# AquaSchematic.net
KiCad netlist of a schematic drawn in EAGLE
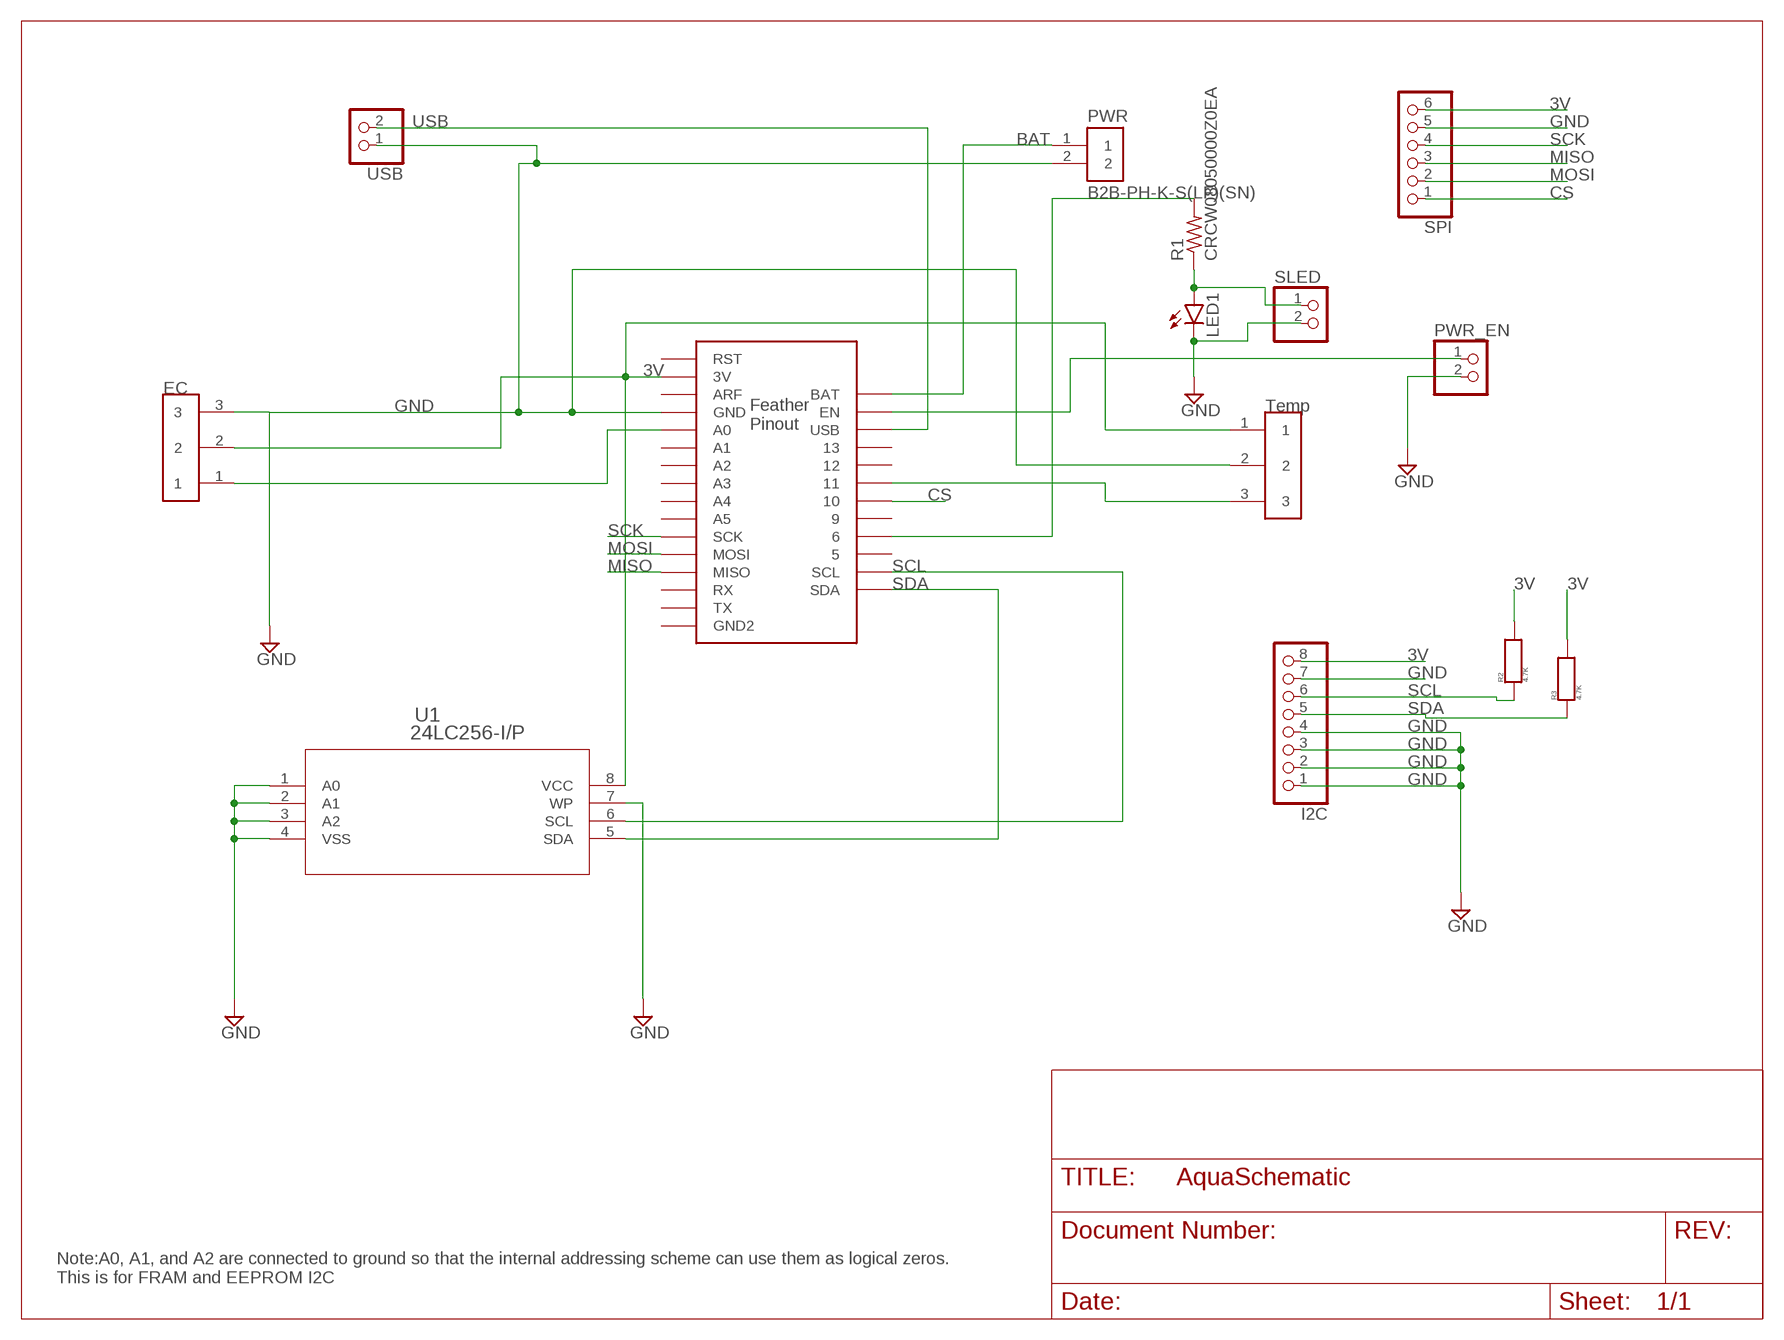
[diagram p0: schematic, sheet 1]

(export (version "E")
  (design (tool "Eeschema 10.0.6"))
  (components
    (comp (ref "EC")
      (value "39773-0003")
      (footprint "eagle-import:39773-0003")
      (libsource (lib "eagle-import") (part "39773-0003"))
    )
    (comp (ref "I2C")
      (value "PINHD-1X8")
      (footprint "eagle-import:1X08")
      (libsource (lib "eagle-import") (part "PINHD-1X8"))
    )
    (comp (ref "LED1")
      (value "LEDCHIP-LED0805")
      (footprint "eagle-import:CHIP-LED0805")
      (libsource (lib "eagle-import") (part "LEDCHIP-LED0805"))
    )
    (comp (ref "PWR")
      (value "B2B-PH-K-S(LF)(SN)")
      (footprint "eagle-import:JST_B2B-PH-K-S(LF)(SN)")
      (fields
        (field (name "DIGI-KEY_PART_NUMBER") "455-1704-ND")
        (field (name "MF") "JST Sales")
        (field (name "MP") "B2B-PH-K-S_LF__SN_")
      )
      (libsource (lib "eagle-import") (part "B2B-PH-K-S(LF)(SN)"))
    )
    (comp (ref "PWR_EN")
      (value "PINHD-1X2")
      (footprint "eagle-import:1X02")
      (libsource (lib "eagle-import") (part "PINHD-1X2"))
    )
    (comp (ref "R1")
      (value "CRCW08050000Z0EA")
      (footprint "eagle-import:RES_0805")
      (fields
        (field (name "DIGIKEY_PART_NUMBER") "541-0.0ATR-ND")
        (field (name "MANUFACTURER") "Vishay Dale")
        (field (name "CREATED_BY") "PCBLayout.com")
      )
      (libsource (lib "eagle-import") (part "CRCW08050000Z0EA"))
    )
    (comp (ref "R2")
      (value "4.7K")
      (footprint "eagle-import:MFR3-4K7FC")
      (libsource (lib "eagle-import") (part "MFR3-4K7FC"))
    )
    (comp (ref "R3")
      (value "4.7K")
      (footprint "eagle-import:MFR3-4K7FC")
      (libsource (lib "eagle-import") (part "MFR3-4K7FC"))
    )
    (comp (ref "SLED")
      (value "PINHD-1X2")
      (footprint "eagle-import:1X02")
      (libsource (lib "eagle-import") (part "PINHD-1X2"))
    )
    (comp (ref "SPI")
      (value "PINHD-1X6")
      (footprint "eagle-import:1X06")
      (libsource (lib "eagle-import") (part "PINHD-1X6"))
    )
    (comp (ref "TEMP")
      (value "39773-0003")
      (footprint "eagle-import:39773-0003")
      (libsource (lib "eagle-import") (part "39773-0003"))
    )
    (comp (ref "U$1")
      (value "FEATHER_M0_PROTO")
      (footprint "eagle-import:FEATHER_MO_PROTO")
      (libsource (lib "eagle-import") (part "FEATHER_M0_PROTO"))
    )
    (comp (ref "U1")
      (value "24LC256-I/P")
      (footprint "eagle-import:PDIP8_300MC")
      (fields (field (name "MANUFACTURER_PART_NUMBER") "24LC256IP"))
      (libsource (lib "eagle-import") (part "24LC256-I/P"))
    )
    (comp (ref "USB")
      (value "PINHD-1X2")
      (footprint "eagle-import:1X02")
      (libsource (lib "eagle-import") (part "PINHD-1X2"))
    )
  )
  (nets
    (net (code "1") (name "/3V") (class "Default")
      (node (ref "EC") (pin "2") (pinfunction "2_2") (pintype "bidirectional"))
      (node (ref "I2C") (pin "8") (pinfunction "8_8") (pintype "passive"))
      (node (ref "R2") (pin "PIN1") (pinfunction "P$1_PIN1") (pintype "bidirectional"))
      (node (ref "R3") (pin "PIN1") (pinfunction "P$1_PIN1") (pintype "bidirectional"))
      (node (ref "SPI") (pin "6") (pinfunction "6_6") (pintype "passive"))
      (node (ref "TEMP") (pin "1") (pinfunction "1_1") (pintype "bidirectional"))
      (node (ref "U$1") (pin "3V") (pinfunction "3V_3V") (pintype "bidirectional"))
      (node (ref "U1") (pin "8") (pinfunction "VCC_8") (pintype "passive"))
    )
    (net (code "2") (name "/BAT") (class "Default")
      (node (ref "PWR") (pin "1") (pinfunction "1_1") (pintype "passive"))
      (node (ref "U$1") (pin "BAT") (pinfunction "BAT_BAT") (pintype "bidirectional"))
    )
    (net (code "3") (name "/CS") (class "Default")
      (node (ref "SPI") (pin "1") (pinfunction "1_1") (pintype "passive"))
      (node (ref "U$1") (pin "10") (pinfunction "10_10") (pintype "bidirectional"))
    )
    (net (code "4") (name "/MISO") (class "Default")
      (node (ref "SPI") (pin "3") (pinfunction "3_3") (pintype "passive"))
      (node (ref "U$1") (pin "MISO") (pinfunction "MISO_MISO") (pintype "bidirectional"))
    )
    (net (code "5") (name "/MOSI") (class "Default")
      (node (ref "SPI") (pin "2") (pinfunction "2_2") (pintype "passive"))
      (node (ref "U$1") (pin "MOSI") (pinfunction "MOSI_MOSI") (pintype "bidirectional"))
    )
    (net (code "6") (name "/SCK") (class "Default")
      (node (ref "SPI") (pin "4") (pinfunction "4_4") (pintype "passive"))
      (node (ref "U$1") (pin "SCK") (pinfunction "SCK_SCK") (pintype "bidirectional"))
    )
    (net (code "7") (name "/SCL") (class "Default")
      (node (ref "I2C") (pin "6") (pinfunction "6_6") (pintype "passive"))
      (node (ref "R2") (pin "PIN2") (pinfunction "P$2_PIN2") (pintype "bidirectional"))
      (node (ref "U$1") (pin "SCL") (pinfunction "SCL_SCL") (pintype "bidirectional"))
      (node (ref "U1") (pin "6") (pinfunction "SCL_6") (pintype "passive"))
    )
    (net (code "8") (name "/SDA") (class "Default")
      (node (ref "I2C") (pin "5") (pinfunction "5_5") (pintype "passive"))
      (node (ref "R3") (pin "PIN2") (pinfunction "P$2_PIN2") (pintype "bidirectional"))
      (node (ref "U$1") (pin "SDA") (pinfunction "SDA_SDA") (pintype "bidirectional"))
      (node (ref "U1") (pin "5") (pinfunction "SDA_5") (pintype "passive"))
    )
    (net (code "9") (name "/USB") (class "Default")
      (node (ref "U$1") (pin "USB") (pinfunction "USB_USB") (pintype "bidirectional"))
      (node (ref "USB") (pin "2") (pinfunction "2_2") (pintype "passive"))
    )
    (net (code "10") (name "GND") (class "Default")
      (node (ref "EC") (pin "3") (pinfunction "3_3") (pintype "bidirectional"))
      (node (ref "I2C") (pin "1") (pinfunction "1_1") (pintype "passive"))
      (node (ref "I2C") (pin "2") (pinfunction "2_2") (pintype "passive"))
      (node (ref "I2C") (pin "3") (pinfunction "3_3") (pintype "passive"))
      (node (ref "I2C") (pin "4") (pinfunction "4_4") (pintype "passive"))
      (node (ref "I2C") (pin "7") (pinfunction "7_7") (pintype "passive"))
      (node (ref "LED1") (pin "C") (pinfunction "C_C") (pintype "passive"))
      (node (ref "PWR") (pin "2") (pinfunction "2_2") (pintype "passive"))
      (node (ref "PWR_EN") (pin "2") (pinfunction "2_2") (pintype "passive"))
      (node (ref "SLED") (pin "2") (pinfunction "2_2") (pintype "passive"))
      (node (ref "SPI") (pin "5") (pinfunction "5_5") (pintype "passive"))
      (node (ref "TEMP") (pin "2") (pinfunction "2_2") (pintype "bidirectional"))
      (node (ref "U$1") (pin "GND") (pinfunction "GND_GND") (pintype "bidirectional"))
      (node (ref "U1") (pin "1") (pinfunction "A0_1") (pintype "passive"))
      (node (ref "U1") (pin "2") (pinfunction "A1_2") (pintype "passive"))
      (node (ref "U1") (pin "3") (pinfunction "A2_3") (pintype "passive"))
      (node (ref "U1") (pin "4") (pinfunction "VSS_4") (pintype "passive"))
      (node (ref "U1") (pin "7") (pinfunction "WP_7") (pintype "passive"))
      (node (ref "USB") (pin "1") (pinfunction "1_1") (pintype "passive"))
    )
    (net (code "11") (name "Net-(EC-Pad1)") (class "Default")
      (node (ref "EC") (pin "1") (pinfunction "1_1") (pintype "bidirectional"))
      (node (ref "U$1") (pin "A0") (pinfunction "A0_A0") (pintype "bidirectional"))
    )
    (net (code "12") (name "Net-(LED1-PadA)") (class "Default")
      (node (ref "LED1") (pin "A") (pinfunction "A_A") (pintype "passive"))
      (node (ref "R1") (pin "1") (pinfunction "1_1") (pintype "passive"))
      (node (ref "SLED") (pin "1") (pinfunction "1_1") (pintype "passive"))
    )
    (net (code "13") (name "Net-(PWR_EN-Pad1)") (class "Default")
      (node (ref "PWR_EN") (pin "1") (pinfunction "1_1") (pintype "passive"))
      (node (ref "U$1") (pin "EN") (pinfunction "EN_EN") (pintype "bidirectional"))
    )
    (net (code "14") (name "Net-(R1-Pad2)") (class "Default")
      (node (ref "R1") (pin "2") (pinfunction "2_2") (pintype "passive"))
      (node (ref "U$1") (pin "6") (pinfunction "6_6") (pintype "bidirectional"))
    )
    (net (code "15") (name "Net-(TEMP-Pad3)") (class "Default")
      (node (ref "TEMP") (pin "3") (pinfunction "3_3") (pintype "bidirectional"))
      (node (ref "U$1") (pin "11") (pinfunction "11_11") (pintype "bidirectional"))
    )
    (net (code "16") (name "unconnected-(U$1-Pad5)") (class "Default")
      (node (ref "U$1") (pin "5") (pinfunction "5_5") (pintype "bidirectional"))
    )
    (net (code "17") (name "unconnected-(U$1-Pad9)") (class "Default")
      (node (ref "U$1") (pin "9") (pinfunction "9_9") (pintype "bidirectional"))
    )
    (net (code "18") (name "unconnected-(U$1-Pad12)") (class "Default")
      (node (ref "U$1") (pin "12") (pinfunction "12_12") (pintype "bidirectional"))
    )
    (net (code "19") (name "unconnected-(U$1-Pad13)") (class "Default")
      (node (ref "U$1") (pin "13") (pinfunction "13_13") (pintype "bidirectional"))
    )
    (net (code "20") (name "unconnected-(U$1-PadA1)") (class "Default")
      (node (ref "U$1") (pin "A1") (pinfunction "A1_A1") (pintype "bidirectional"))
    )
    (net (code "21") (name "unconnected-(U$1-PadA2)") (class "Default")
      (node (ref "U$1") (pin "A2") (pinfunction "A2_A2") (pintype "bidirectional"))
    )
    (net (code "22") (name "unconnected-(U$1-PadA3)") (class "Default")
      (node (ref "U$1") (pin "A3") (pinfunction "A3_A3") (pintype "bidirectional"))
    )
    (net (code "23") (name "unconnected-(U$1-PadA4)") (class "Default")
      (node (ref "U$1") (pin "A4") (pinfunction "A4_A4") (pintype "bidirectional"))
    )
    (net (code "24") (name "unconnected-(U$1-PadA5)") (class "Default")
      (node (ref "U$1") (pin "A5") (pinfunction "A5_A5") (pintype "bidirectional"))
    )
    (net (code "25") (name "unconnected-(U$1-PadARF)") (class "Default")
      (node (ref "U$1") (pin "ARF") (pinfunction "ARF_ARF") (pintype "bidirectional"))
    )
    (net (code "26") (name "unconnected-(U$1-PadGND2)") (class "Default")
      (node (ref "U$1") (pin "GND2") (pinfunction "GND2_GND2") (pintype "bidirectional"))
    )
    (net (code "27") (name "unconnected-(U$1-PadRST)") (class "Default")
      (node (ref "U$1") (pin "RST") (pinfunction "RST_RST") (pintype "bidirectional"))
    )
    (net (code "28") (name "unconnected-(U$1-PadRX)") (class "Default")
      (node (ref "U$1") (pin "RX") (pinfunction "RX_RX") (pintype "bidirectional"))
    )
    (net (code "29") (name "unconnected-(U$1-PadTX)") (class "Default")
      (node (ref "U$1") (pin "TX") (pinfunction "TX_TX") (pintype "bidirectional"))
    )
  )
)
